# mobo-dbus-combined.net
KiCad netlist of a schematic drawn in EAGLE
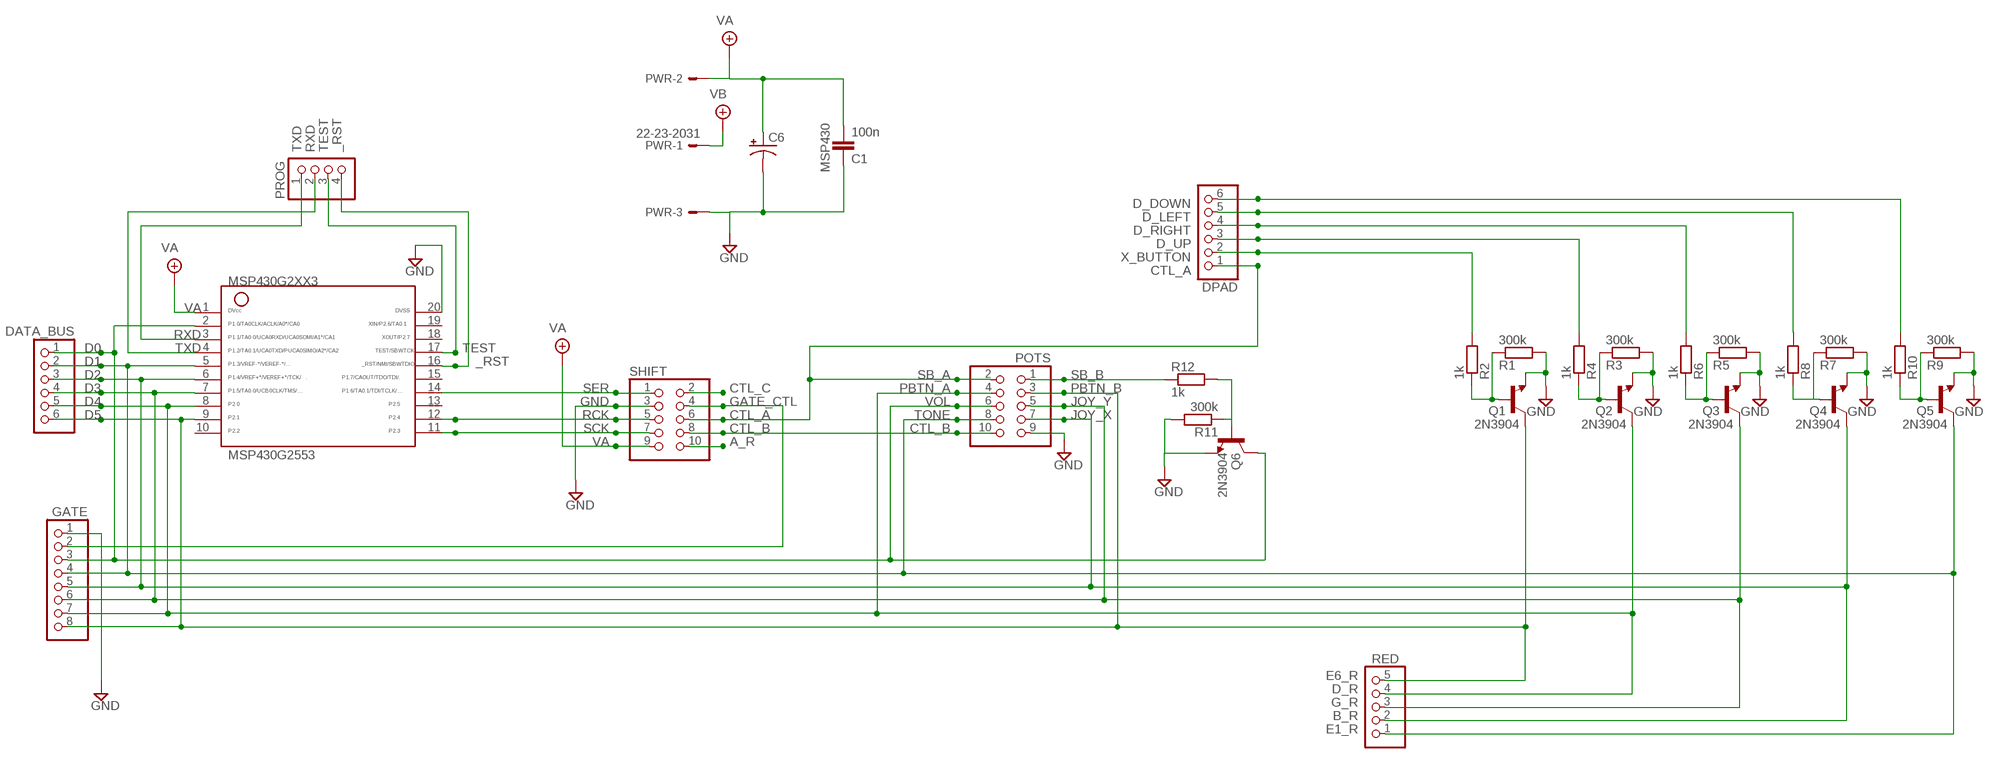
[diagram p0: schematic, sheet 1]

(export (version "E")
  (design (tool "Eeschema 10.0.6"))
  (components
    (comp (ref "C1")
      (value "100n")
      (footprint "eagle-import:050X030_050_3")
      (libsource (lib "eagle-import") (part "050X030_050"))
    )
    (comp (ref "C6")
      (value "0501")
      (footprint "eagle-import:050_020_1")
      (libsource (lib "eagle-import") (part "0501"))
    )
    (comp (ref "DATA_BUS")
      (value "PINHD-1X6")
      (footprint "eagle-import:1X06")
      (libsource (lib "eagle-import") (part "PINHD-1X6"))
    )
    (comp (ref "DPAD")
      (value "PINHD-1X6")
      (footprint "eagle-import:1X06")
      (libsource (lib "eagle-import") (part "PINHD-1X6"))
    )
    (comp (ref "GATE")
      (value "PINHD-1X8")
      (footprint "eagle-import:1X08")
      (libsource (lib "eagle-import") (part "PINHD-1X8"))
    )
    (comp (ref "MSP430G2553")
      (value "G2XX3---N20")
      (footprint "eagle-import:N20")
      (libsource (lib "eagle-import") (part "G2XX3---N20"))
    )
    (comp (ref "POTS")
      (value "PINHD-2X5")
      (footprint "eagle-import:2X05")
      (libsource (lib "eagle-import") (part "PINHD-2X5"))
    )
    (comp (ref "PROG")
      (value "PINHD-1X4")
      (footprint "eagle-import:1X04")
      (libsource (lib "eagle-import") (part "PINHD-1X4"))
    )
    (comp (ref "PWR")
      (value "22-23-2031")
      (footprint "eagle-import:22-23-2031")
      (fields (field (name "MF") "MOLEX"))
      (libsource (lib "eagle-import") (part "22-23-2031"))
    )
    (comp (ref "Q1")
      (value "2N3904")
      (footprint "eagle-import:TO92-")
      (libsource (lib "eagle-import") (part "2N3904"))
    )
    (comp (ref "Q2")
      (value "2N3904")
      (footprint "eagle-import:TO92-")
      (libsource (lib "eagle-import") (part "2N3904"))
    )
    (comp (ref "Q3")
      (value "2N3904")
      (footprint "eagle-import:TO92-")
      (libsource (lib "eagle-import") (part "2N3904"))
    )
    (comp (ref "Q4")
      (value "2N3904")
      (footprint "eagle-import:TO92-")
      (libsource (lib "eagle-import") (part "2N3904"))
    )
    (comp (ref "Q5")
      (value "2N3904")
      (footprint "eagle-import:TO92-")
      (libsource (lib "eagle-import") (part "2N3904"))
    )
    (comp (ref "Q6")
      (value "2N3904")
      (footprint "eagle-import:TO92-")
      (libsource (lib "eagle-import") (part "2N3904"))
    )
    (comp (ref "R1")
      (value "300k")
      (footprint "eagle-import:R0207_1V")
      (libsource (lib "eagle-import") (part "6MM-EU1"))
    )
    (comp (ref "R2")
      (value "1k")
      (footprint "eagle-import:R0207_1V")
      (libsource (lib "eagle-import") (part "6MM-EU1"))
    )
    (comp (ref "R3")
      (value "300k")
      (footprint "eagle-import:R0207_1V")
      (libsource (lib "eagle-import") (part "6MM-EU1"))
    )
    (comp (ref "R4")
      (value "1k")
      (footprint "eagle-import:R0207_1V")
      (libsource (lib "eagle-import") (part "6MM-EU1"))
    )
    (comp (ref "R5")
      (value "300k")
      (footprint "eagle-import:R0207_1V")
      (libsource (lib "eagle-import") (part "6MM-EU1"))
    )
    (comp (ref "R6")
      (value "1k")
      (footprint "eagle-import:R0207_1V")
      (libsource (lib "eagle-import") (part "6MM-EU1"))
    )
    (comp (ref "R7")
      (value "300k")
      (footprint "eagle-import:R0207_1V")
      (libsource (lib "eagle-import") (part "6MM-EU1"))
    )
    (comp (ref "R8")
      (value "1k")
      (footprint "eagle-import:R0207_1V")
      (libsource (lib "eagle-import") (part "6MM-EU1"))
    )
    (comp (ref "R9")
      (value "300k")
      (footprint "eagle-import:R0207_1V")
      (libsource (lib "eagle-import") (part "6MM-EU1"))
    )
    (comp (ref "R10")
      (value "1k")
      (footprint "eagle-import:R0207_1V")
      (libsource (lib "eagle-import") (part "6MM-EU1"))
    )
    (comp (ref "R11")
      (value "300k")
      (footprint "eagle-import:R0207_1V")
      (libsource (lib "eagle-import") (part "6MM-EU1"))
    )
    (comp (ref "R12")
      (value "1k")
      (footprint "eagle-import:R0207_1V")
      (libsource (lib "eagle-import") (part "6MM-EU1"))
    )
    (comp (ref "RED")
      (value "PINHD-1X5")
      (footprint "eagle-import:1X05")
      (libsource (lib "eagle-import") (part "PINHD-1X5"))
    )
    (comp (ref "SHIFT")
      (value "PINHD-2X5")
      (footprint "eagle-import:2X05")
      (libsource (lib "eagle-import") (part "PINHD-2X5"))
    )
  )
  (nets
    (net (code "1") (name "/CTL_A") (class "Default")
      (node (ref "DPAD") (pin "1") (pinfunction "1_1") (pintype "passive"))
      (node (ref "POTS") (pin "2") (pinfunction "2_2") (pintype "passive"))
      (node (ref "SHIFT") (pin "6") (pinfunction "6_6") (pintype "passive"))
    )
    (net (code "2") (name "/CTL_B") (class "Default")
      (node (ref "POTS") (pin "10") (pinfunction "10_10") (pintype "passive"))
      (node (ref "SHIFT") (pin "8") (pinfunction "8_8") (pintype "passive"))
    )
    (net (code "3") (name "/CTL_C") (class "Default")
      (node (ref "SHIFT") (pin "2") (pinfunction "2_2") (pintype "passive"))
    )
    (net (code "4") (name "/D0") (class "Default")
      (node (ref "DATA_BUS") (pin "1") (pinfunction "1_1") (pintype "passive"))
      (node (ref "GATE") (pin "3") (pinfunction "3_3") (pintype "passive"))
      (node (ref "MSP430G2553") (pin "2") (pinfunction "2_2") (pintype "bidirectional"))
      (node (ref "POTS") (pin "6") (pinfunction "6_6") (pintype "passive"))
      (node (ref "Q6") (pin "1") (pinfunction "C_1") (pintype "passive"))
      (node (ref "SHIFT") (pin "10") (pinfunction "10_10") (pintype "passive"))
    )
    (net (code "5") (name "/D1") (class "Default")
      (node (ref "DATA_BUS") (pin "2") (pinfunction "2_2") (pintype "passive"))
      (node (ref "GATE") (pin "4") (pinfunction "4_4") (pintype "passive"))
      (node (ref "MSP430G2553") (pin "5") (pinfunction "5_5") (pintype "bidirectional"))
      (node (ref "POTS") (pin "8") (pinfunction "8_8") (pintype "passive"))
      (node (ref "Q5") (pin "1") (pinfunction "C_1") (pintype "passive"))
      (node (ref "RED") (pin "1") (pinfunction "1_1") (pintype "passive"))
    )
    (net (code "6") (name "/D2") (class "Default")
      (node (ref "DATA_BUS") (pin "3") (pinfunction "3_3") (pintype "passive"))
      (node (ref "GATE") (pin "5") (pinfunction "5_5") (pintype "passive"))
      (node (ref "MSP430G2553") (pin "6") (pinfunction "6_6") (pintype "bidirectional"))
      (node (ref "POTS") (pin "7") (pinfunction "7_7") (pintype "passive"))
      (node (ref "Q4") (pin "1") (pinfunction "C_1") (pintype "passive"))
      (node (ref "RED") (pin "2") (pinfunction "2_2") (pintype "passive"))
    )
    (net (code "7") (name "/D3") (class "Default")
      (node (ref "DATA_BUS") (pin "4") (pinfunction "4_4") (pintype "passive"))
      (node (ref "GATE") (pin "6") (pinfunction "6_6") (pintype "passive"))
      (node (ref "MSP430G2553") (pin "7") (pinfunction "7_7") (pintype "bidirectional"))
      (node (ref "POTS") (pin "5") (pinfunction "5_5") (pintype "passive"))
      (node (ref "Q3") (pin "1") (pinfunction "C_1") (pintype "passive"))
      (node (ref "RED") (pin "3") (pinfunction "3_3") (pintype "passive"))
    )
    (net (code "8") (name "/D4") (class "Default")
      (node (ref "DATA_BUS") (pin "5") (pinfunction "5_5") (pintype "passive"))
      (node (ref "GATE") (pin "7") (pinfunction "7_7") (pintype "passive"))
      (node (ref "MSP430G2553") (pin "8") (pinfunction "8_8") (pintype "bidirectional"))
      (node (ref "POTS") (pin "4") (pinfunction "4_4") (pintype "passive"))
      (node (ref "Q2") (pin "1") (pinfunction "C_1") (pintype "passive"))
      (node (ref "RED") (pin "4") (pinfunction "4_4") (pintype "passive"))
    )
    (net (code "9") (name "/D5") (class "Default")
      (node (ref "DATA_BUS") (pin "6") (pinfunction "6_6") (pintype "passive"))
      (node (ref "GATE") (pin "8") (pinfunction "8_8") (pintype "passive"))
      (node (ref "MSP430G2553") (pin "9") (pinfunction "9_9") (pintype "bidirectional"))
      (node (ref "POTS") (pin "3") (pinfunction "3_3") (pintype "passive"))
      (node (ref "Q1") (pin "1") (pinfunction "C_1") (pintype "passive"))
      (node (ref "RED") (pin "5") (pinfunction "5_5") (pintype "passive"))
    )
    (net (code "10") (name "/D_DOWN") (class "Default")
      (node (ref "DPAD") (pin "6") (pinfunction "6_6") (pintype "passive"))
      (node (ref "R10") (pin "2") (pinfunction "2_2") (pintype "passive"))
    )
    (net (code "11") (name "/D_LEFT") (class "Default")
      (node (ref "DPAD") (pin "5") (pinfunction "5_5") (pintype "passive"))
      (node (ref "R8") (pin "2") (pinfunction "2_2") (pintype "passive"))
    )
    (net (code "12") (name "/D_RIGHT") (class "Default")
      (node (ref "DPAD") (pin "4") (pinfunction "4_4") (pintype "passive"))
      (node (ref "R6") (pin "2") (pinfunction "2_2") (pintype "passive"))
    )
    (net (code "13") (name "/D_UP") (class "Default")
      (node (ref "DPAD") (pin "3") (pinfunction "3_3") (pintype "passive"))
      (node (ref "R4") (pin "2") (pinfunction "2_2") (pintype "passive"))
    )
    (net (code "14") (name "/GATE_CTL") (class "Default")
      (node (ref "GATE") (pin "2") (pinfunction "2_2") (pintype "passive"))
      (node (ref "SHIFT") (pin "4") (pinfunction "4_4") (pintype "passive"))
    )
    (net (code "15") (name "/RCK") (class "Default")
      (node (ref "MSP430G2553") (pin "12") (pinfunction "12_12") (pintype "bidirectional"))
      (node (ref "SHIFT") (pin "5") (pinfunction "5_5") (pintype "passive"))
    )
    (net (code "16") (name "/RXD") (class "Default")
      (node (ref "MSP430G2553") (pin "3") (pinfunction "3_3") (pintype "bidirectional"))
      (node (ref "PROG") (pin "1") (pinfunction "1_1") (pintype "passive"))
    )
    (net (code "17") (name "/SCK") (class "Default")
      (node (ref "MSP430G2553") (pin "11") (pinfunction "11_11") (pintype "bidirectional"))
      (node (ref "SHIFT") (pin "7") (pinfunction "7_7") (pintype "passive"))
    )
    (net (code "18") (name "/SER") (class "Default")
      (node (ref "MSP430G2553") (pin "14") (pinfunction "14_14") (pintype "bidirectional"))
      (node (ref "SHIFT") (pin "1") (pinfunction "1_1") (pintype "passive"))
    )
    (net (code "19") (name "/TEST") (class "Default")
      (node (ref "MSP430G2553") (pin "17") (pinfunction "17_17") (pintype "bidirectional"))
      (node (ref "PROG") (pin "3") (pinfunction "3_3") (pintype "passive"))
    )
    (net (code "20") (name "/TXD") (class "Default")
      (node (ref "MSP430G2553") (pin "4") (pinfunction "4_4") (pintype "bidirectional"))
      (node (ref "PROG") (pin "2") (pinfunction "2_2") (pintype "passive"))
    )
    (net (code "21") (name "/X_BUTTON") (class "Default")
      (node (ref "DPAD") (pin "2") (pinfunction "2_2") (pintype "passive"))
      (node (ref "R2") (pin "2") (pinfunction "2_2") (pintype "passive"))
    )
    (net (code "22") (name "/_RST") (class "Default")
      (node (ref "MSP430G2553") (pin "16") (pinfunction "16_16") (pintype "bidirectional"))
      (node (ref "PROG") (pin "4") (pinfunction "4_4") (pintype "passive"))
    )
    (net (code "23") (name "GND") (class "Default")
      (node (ref "C1") (pin "1") (pinfunction "1_1") (pintype "passive"))
      (node (ref "C6") (pin "-") (pinfunction "-_-") (pintype "passive"))
      (node (ref "GATE") (pin "1") (pinfunction "1_1") (pintype "passive"))
      (node (ref "MSP430G2553") (pin "20") (pinfunction "20_20") (pintype "bidirectional"))
      (node (ref "POTS") (pin "9") (pinfunction "9_9") (pintype "passive"))
      (node (ref "PWR") (pin "3") (pinfunction "S_3") (pintype "passive"))
      (node (ref "Q1") (pin "3") (pinfunction "E_3") (pintype "passive"))
      (node (ref "Q2") (pin "3") (pinfunction "E_3") (pintype "passive"))
      (node (ref "Q3") (pin "3") (pinfunction "E_3") (pintype "passive"))
      (node (ref "Q4") (pin "3") (pinfunction "E_3") (pintype "passive"))
      (node (ref "Q5") (pin "3") (pinfunction "E_3") (pintype "passive"))
      (node (ref "Q6") (pin "3") (pinfunction "E_3") (pintype "passive"))
      (node (ref "R1") (pin "2") (pinfunction "2_2") (pintype "passive"))
      (node (ref "R11") (pin "2") (pinfunction "2_2") (pintype "passive"))
      (node (ref "R3") (pin "2") (pinfunction "2_2") (pintype "passive"))
      (node (ref "R5") (pin "2") (pinfunction "2_2") (pintype "passive"))
      (node (ref "R7") (pin "2") (pinfunction "2_2") (pintype "passive"))
      (node (ref "R9") (pin "2") (pinfunction "2_2") (pintype "passive"))
      (node (ref "SHIFT") (pin "3") (pinfunction "3_3") (pintype "passive"))
    )
    (net (code "24") (name "Net-(POTS-Pad1)") (class "Default")
      (node (ref "POTS") (pin "1") (pinfunction "1_1") (pintype "passive"))
      (node (ref "R12") (pin "1") (pinfunction "1_1") (pintype "passive"))
    )
    (net (code "25") (name "Net-(Q1-B)") (class "Default")
      (node (ref "Q1") (pin "2") (pinfunction "B_2") (pintype "passive"))
      (node (ref "R1") (pin "1") (pinfunction "1_1") (pintype "passive"))
      (node (ref "R2") (pin "1") (pinfunction "1_1") (pintype "passive"))
    )
    (net (code "26") (name "Net-(Q2-B)") (class "Default")
      (node (ref "Q2") (pin "2") (pinfunction "B_2") (pintype "passive"))
      (node (ref "R3") (pin "1") (pinfunction "1_1") (pintype "passive"))
      (node (ref "R4") (pin "1") (pinfunction "1_1") (pintype "passive"))
    )
    (net (code "27") (name "Net-(Q3-B)") (class "Default")
      (node (ref "Q3") (pin "2") (pinfunction "B_2") (pintype "passive"))
      (node (ref "R5") (pin "1") (pinfunction "1_1") (pintype "passive"))
      (node (ref "R6") (pin "1") (pinfunction "1_1") (pintype "passive"))
    )
    (net (code "28") (name "Net-(Q4-B)") (class "Default")
      (node (ref "Q4") (pin "2") (pinfunction "B_2") (pintype "passive"))
      (node (ref "R7") (pin "1") (pinfunction "1_1") (pintype "passive"))
      (node (ref "R8") (pin "1") (pinfunction "1_1") (pintype "passive"))
    )
    (net (code "29") (name "Net-(Q5-B)") (class "Default")
      (node (ref "Q5") (pin "2") (pinfunction "B_2") (pintype "passive"))
      (node (ref "R10") (pin "1") (pinfunction "1_1") (pintype "passive"))
      (node (ref "R9") (pin "1") (pinfunction "1_1") (pintype "passive"))
    )
    (net (code "30") (name "Net-(Q6-B)") (class "Default")
      (node (ref "Q6") (pin "2") (pinfunction "B_2") (pintype "passive"))
      (node (ref "R11") (pin "1") (pinfunction "1_1") (pintype "passive"))
      (node (ref "R12") (pin "2") (pinfunction "2_2") (pintype "passive"))
    )
    (net (code "31") (name "VA") (class "Default")
      (node (ref "C1") (pin "2") (pinfunction "2_2") (pintype "passive"))
      (node (ref "C6") (pin "+") (pinfunction "+_+") (pintype "passive"))
      (node (ref "MSP430G2553") (pin "1") (pinfunction "1_1") (pintype "bidirectional"))
      (node (ref "PWR") (pin "2") (pinfunction "S_2") (pintype "passive"))
      (node (ref "SHIFT") (pin "9") (pinfunction "9_9") (pintype "passive"))
    )
    (net (code "32") (name "VB") (class "Default")
      (node (ref "PWR") (pin "1") (pinfunction "S_1") (pintype "passive"))
    )
    (net (code "33") (name "unconnected-(MSP430G2553-Pad10)") (class "Default")
      (node (ref "MSP430G2553") (pin "10") (pinfunction "10_10") (pintype "bidirectional"))
    )
    (net (code "34") (name "unconnected-(MSP430G2553-Pad13)") (class "Default")
      (node (ref "MSP430G2553") (pin "13") (pinfunction "13_13") (pintype "bidirectional"))
    )
    (net (code "35") (name "unconnected-(MSP430G2553-Pad15)") (class "Default")
      (node (ref "MSP430G2553") (pin "15") (pinfunction "15_15") (pintype "bidirectional"))
    )
    (net (code "36") (name "unconnected-(MSP430G2553-Pad18)") (class "Default")
      (node (ref "MSP430G2553") (pin "18") (pinfunction "18_18") (pintype "bidirectional"))
    )
    (net (code "37") (name "unconnected-(MSP430G2553-Pad19)") (class "Default")
      (node (ref "MSP430G2553") (pin "19") (pinfunction "19_19") (pintype "bidirectional"))
    )
  )
)
